# LcsNodes-Building-Block-USB-Serial-IO.net
KiCad netlist of a schematic drawn in EasyEDA
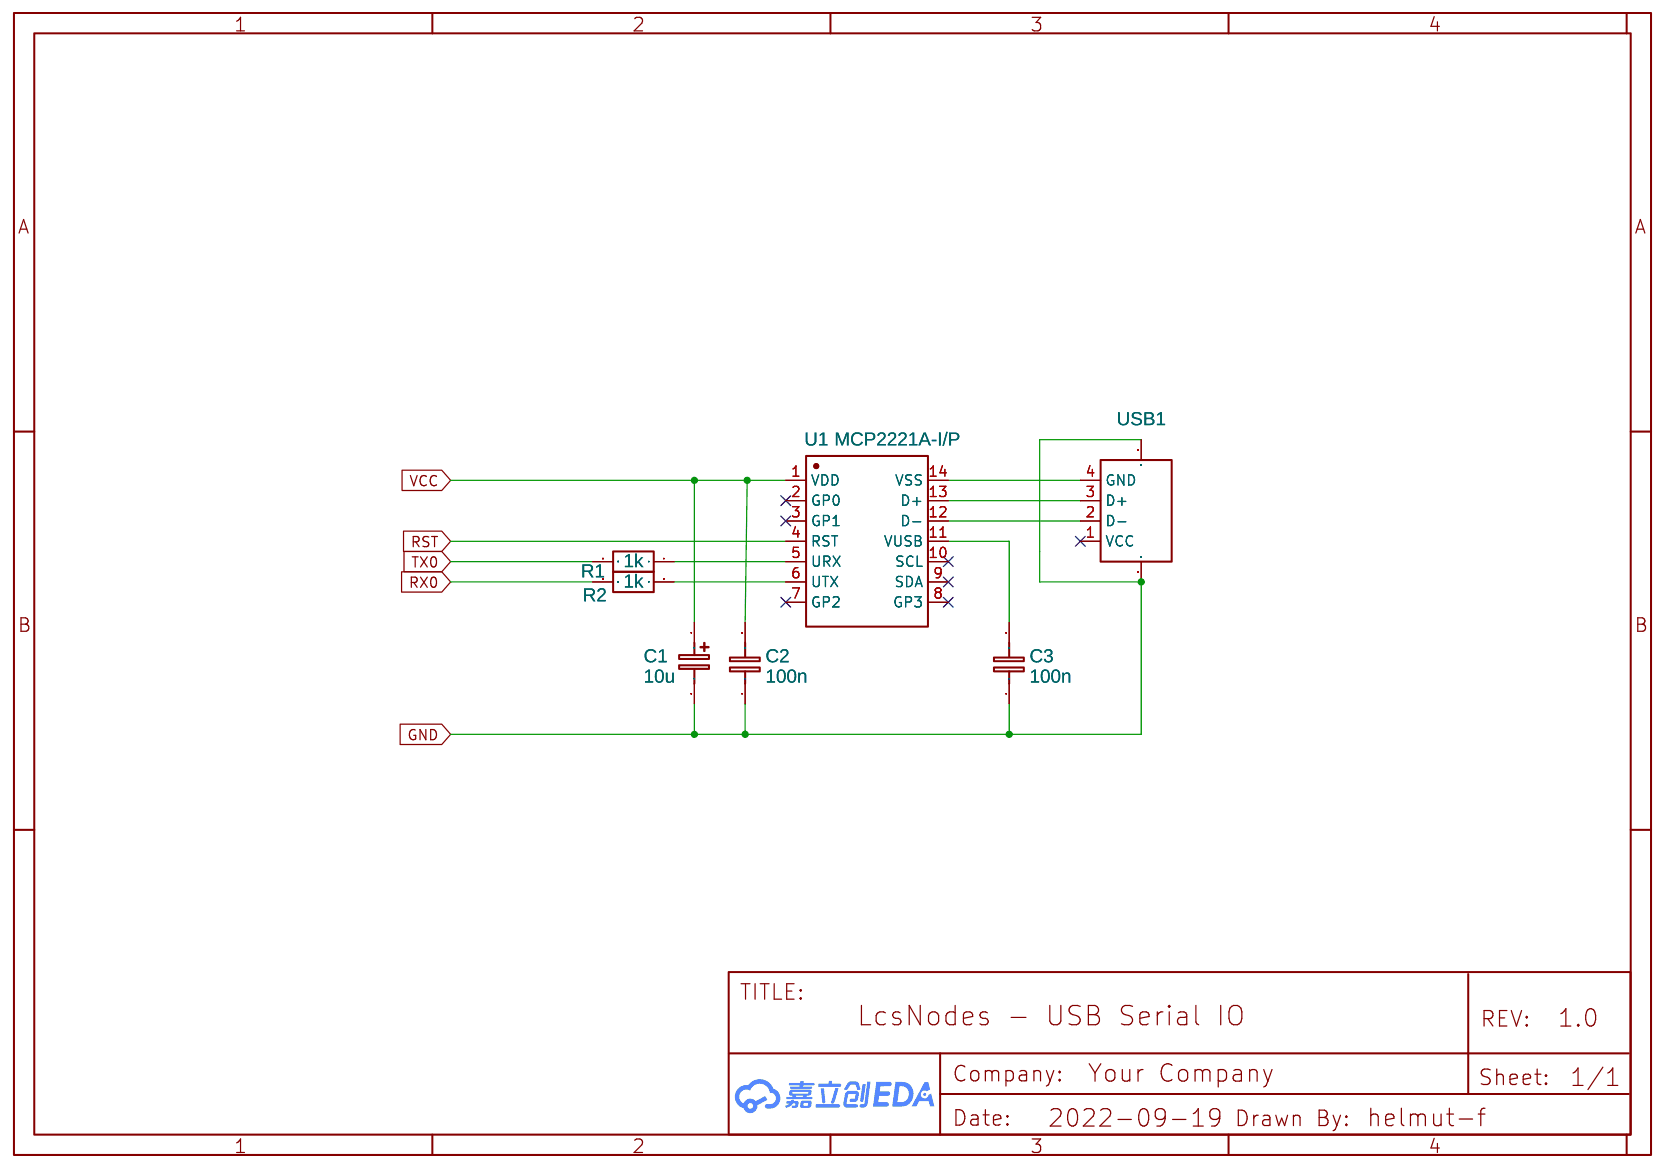
[diagram p0: schematic sheet]

(export (version "E")
  (design (tool "Eeschema 10.0.6"))
  (components
    (comp (ref "C1") (value "10u") (libsource (lib "") (part "CE_TH_D4.0×F1.5_EU")))
    (comp (ref "C2") (value "100n") (libsource (lib "") (part "C_0603_EU")))
    (comp (ref "C3") (value "100n") (libsource (lib "") (part "C_0603_EU")))
    (comp (ref "R1") (value "1k") (libsource (lib "") (part "R_AXIAL-0.3_EU")))
    (comp (ref "R2") (value "1k") (libsource (lib "") (part "R_AXIAL-0.3_EU")))
    (comp (ref "U1") (value "MCP2221A-I/P") (libsource (lib "") (part "MCP2221A-I/P")))
    (comp (ref "USB1")
      (value "USB-Type A_Male")
      (fields (field (name "Manufacturer Part") "USB-05") (field (name "Manufacturer") "SOFNG"))
      (libsource (lib "") (part "USB-Type A_Male"))
    )
  )
  (nets
    (net (code "1") (name "GND") (class "Default")
      (node (ref "C1") (pin "2") (pinfunction "2_2") (pintype "unspecified"))
      (node (ref "C2") (pin "1") (pinfunction "1_1") (pintype "unspecified"))
      (node (ref "C3") (pin "1") (pinfunction "1_1") (pintype "unspecified"))
      (node (ref "USB1") (pin "5") (pinfunction "5_5") (pintype "unspecified"))
      (node (ref "USB1") (pin "6") (pinfunction "6_6") (pintype "unspecified"))
    )
    (net (code "2") (name "Net-(U1-D+)") (class "Default")
      (node (ref "U1") (pin "13") (pinfunction "D+_13") (pintype "unspecified"))
      (node (ref "USB1") (pin "3") (pinfunction "D+_3") (pintype "input"))
    )
    (net (code "3") (name "Net-(U1-D-)") (class "Default")
      (node (ref "U1") (pin "12") (pinfunction "D-_12") (pintype "unspecified"))
      (node (ref "USB1") (pin "2") (pinfunction "D-_2") (pintype "input"))
    )
    (net (code "4") (name "Net-(U1-URX)") (class "Default")
      (node (ref "R1") (pin "1") (pinfunction "1_1") (pintype "unspecified"))
      (node (ref "U1") (pin "5") (pinfunction "URX_5") (pintype "unspecified"))
    )
    (net (code "5") (name "Net-(U1-UTX)") (class "Default")
      (node (ref "R2") (pin "1") (pinfunction "1_1") (pintype "unspecified"))
      (node (ref "U1") (pin "6") (pinfunction "UTX_6") (pintype "unspecified"))
    )
    (net (code "6") (name "Net-(U1-VSS)") (class "Default")
      (node (ref "U1") (pin "14") (pinfunction "VSS_14") (pintype "unspecified"))
      (node (ref "USB1") (pin "4") (pinfunction "GND_4") (pintype "input"))
    )
    (net (code "7") (name "Net-(U1-VUSB)") (class "Default")
      (node (ref "C3") (pin "2") (pinfunction "2_2") (pintype "unspecified"))
      (node (ref "U1") (pin "11") (pinfunction "VUSB_11") (pintype "unspecified"))
    )
    (net (code "8") (name "RST") (class "Default")
      (node (ref "U1") (pin "4") (pinfunction "RST_4") (pintype "unspecified"))
    )
    (net (code "9") (name "RX0") (class "Default")
      (node (ref "R2") (pin "2") (pinfunction "2_2") (pintype "unspecified"))
    )
    (net (code "10") (name "TX0") (class "Default")
      (node (ref "R1") (pin "2") (pinfunction "2_2") (pintype "unspecified"))
    )
    (net (code "11") (name "VCC") (class "Default")
      (node (ref "C1") (pin "1") (pinfunction "1_1") (pintype "unspecified"))
      (node (ref "C2") (pin "2") (pinfunction "2_2") (pintype "unspecified"))
      (node (ref "U1") (pin "1") (pinfunction "VDD_1") (pintype "unspecified"))
    )
    (net (code "12") (name "unconnected-(U1-GP0-Pad2)") (class "Default")
      (node (ref "U1") (pin "2") (pinfunction "GP0_2") (pintype "unspecified+no_connect"))
    )
    (net (code "13") (name "unconnected-(U1-GP1-Pad3)") (class "Default")
      (node (ref "U1") (pin "3") (pinfunction "GP1_3") (pintype "unspecified+no_connect"))
    )
    (net (code "14") (name "unconnected-(U1-GP2-Pad7)") (class "Default")
      (node (ref "U1") (pin "7") (pinfunction "GP2_7") (pintype "unspecified+no_connect"))
    )
    (net (code "15") (name "unconnected-(U1-GP3-Pad8)") (class "Default")
      (node (ref "U1") (pin "8") (pinfunction "GP3_8") (pintype "unspecified+no_connect"))
    )
    (net (code "16") (name "unconnected-(U1-SCL-Pad10)") (class "Default")
      (node (ref "U1") (pin "10") (pinfunction "SCL_10") (pintype "unspecified+no_connect"))
    )
    (net (code "17") (name "unconnected-(U1-SDA-Pad9)") (class "Default")
      (node (ref "U1") (pin "9") (pinfunction "SDA_9") (pintype "unspecified+no_connect"))
    )
    (net (code "18") (name "unconnected-(USB1-VCC-Pad1)") (class "Default")
      (node (ref "USB1") (pin "1") (pinfunction "VCC_1") (pintype "input+no_connect"))
    )
  )
)
